# class_ab.net
KiCad netlist of a schematic drawn in Altium Designer
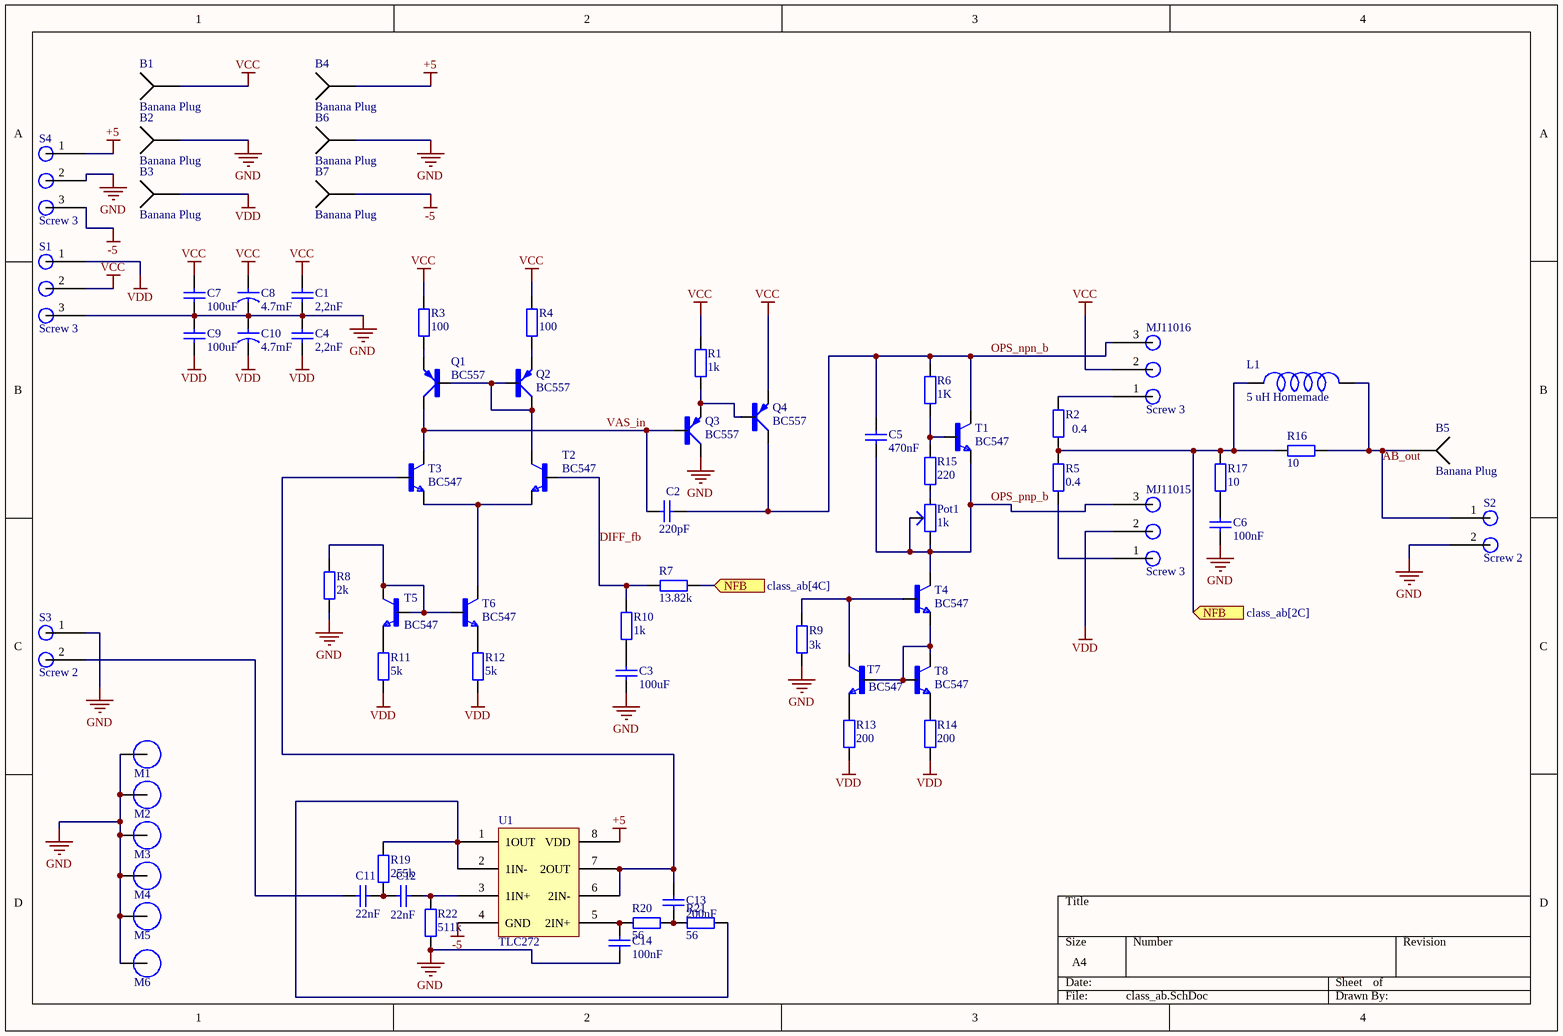
[diagram p0: class_ab.SchDoc]

(export (version "E")
  (design (tool "Eeschema 10.0.6"))
  (components
    (comp (ref "B1")
      (value "Banana Plug")
      (footprint "Banana Plug On top")
      (libsource (lib "AAURacing") (part "Banana Plug"))
    )
    (comp (ref "B2")
      (value "Banana Plug")
      (footprint "Banana Plug On top")
      (libsource (lib "AAURacing") (part "Banana Plug"))
    )
    (comp (ref "B3")
      (value "Banana Plug")
      (footprint "Banana Plug On top")
      (libsource (lib "AAURacing") (part "Banana Plug"))
    )
    (comp (ref "B4")
      (value "Banana Plug")
      (footprint "Banana Plug On top")
      (libsource (lib "AAURacing") (part "Banana Plug"))
    )
    (comp (ref "B5")
      (value "Banana Plug")
      (footprint "Banana Plug On top")
      (libsource (lib "AAURacing") (part "Banana Plug"))
    )
    (comp (ref "B6")
      (value "Banana Plug")
      (footprint "Banana Plug On top")
      (libsource (lib "AAURacing") (part "Banana Plug"))
    )
    (comp (ref "B7")
      (value "Banana Plug")
      (footprint "Banana Plug On top")
      (libsource (lib "AAURacing") (part "Banana Plug"))
    )
    (comp (ref "C1")
      (value "Cap")
      (footprint "Cap-1")
      (fields (field (name "CAPACITY") "2,2nF"))
      (libsource (lib "AAURacing") (part "Capacitor 1 space"))
    )
    (comp (ref "C2")
      (value "Cap")
      (footprint "Cap-0")
      (fields (field (name "CAPACITY") "220pF"))
      (libsource (lib "AAURacing") (part "Capacitor 0 space"))
    )
    (comp (ref "C3")
      (value "Cap")
      (footprint "Cap Ø8")
      (fields (field (name "CAPACITY") "100uF"))
      (libsource (lib "AAURacing") (part "Capacitor unpolarized"))
    )
    (comp (ref "C4")
      (value "Cap")
      (footprint "Cap-1")
      (fields (field (name "CAPACITY") "2,2nF"))
      (libsource (lib "AAURacing") (part "Capacitor 1 space"))
    )
    (comp (ref "C5")
      (value "Cap")
      (footprint "Cap-1")
      (fields (field (name "CAPACITY") "470nF"))
      (libsource (lib "AAURacing") (part "Capacitor 1 space"))
    )
    (comp (ref "C6")
      (value "Cap")
      (footprint "Cap-1")
      (fields (field (name "CAPACITY") "100nF"))
      (libsource (lib "AAURacing") (part "Capacitor 1 space"))
    )
    (comp (ref "C7")
      (value "Cap")
      (footprint "Cap Ø8")
      (fields (field (name "CAPACITY") "100uF"))
      (libsource (lib "AAURacing") (part "Capacitor unpolarized"))
    )
    (comp (ref "C8")
      (value "Cap")
      (footprint "Cap Lyt Ø18")
      (fields (field (name "CAPACITY") "4.7mF"))
      (libsource (lib "AAURacing") (part "Capacitor electrolytic"))
    )
    (comp (ref "C9")
      (value "Cap")
      (footprint "Cap Ø8")
      (fields (field (name "CAPACITY") "100uF"))
      (libsource (lib "AAURacing") (part "Capacitor unpolarized"))
    )
    (comp (ref "C10")
      (value "Cap")
      (footprint "Cap Lyt Ø18")
      (fields (field (name "CAPACITY") "4.7mF"))
      (libsource (lib "AAURacing") (part "Capacitor electrolytic"))
    )
    (comp (ref "C11")
      (value "Cap")
      (footprint "Cap-1")
      (fields (field (name "CAPACITY") "22nF"))
      (libsource (lib "AAURacing") (part "Capacitor 1 space"))
    )
    (comp (ref "C12")
      (value "Cap")
      (footprint "Cap-1")
      (fields (field (name "CAPACITY") "22nF"))
      (libsource (lib "AAURacing") (part "Capacitor 1 space"))
    )
    (comp (ref "C13")
      (value "Cap")
      (footprint "Cap-1")
      (fields (field (name "CAPACITY") "200nF"))
      (libsource (lib "AAURacing") (part "Capacitor 1 space"))
    )
    (comp (ref "C14")
      (value "Cap")
      (footprint "Cap-1")
      (fields (field (name "CAPACITY") "100nF"))
      (libsource (lib "AAURacing") (part "Capacitor 1 space"))
    )
    (comp (ref "L1")
      (value "5 uH Homemade")
      (footprint "homecooked inductor")
      (libsource (lib "esd410") (part "homemade inductor"))
    )
    (comp (ref "M1")
      (value "Screw Hole")
      (footprint "M3 Hole")
      (libsource (lib "AAURacing") (part "Screw Hole"))
    )
    (comp (ref "M2")
      (value "Screw Hole")
      (footprint "M3 Hole")
      (libsource (lib "AAURacing") (part "Screw Hole"))
    )
    (comp (ref "M3")
      (value "Screw Hole")
      (footprint "M3 Hole")
      (libsource (lib "AAURacing") (part "Screw Hole"))
    )
    (comp (ref "M4")
      (value "Screw Hole")
      (footprint "M3 Hole")
      (libsource (lib "AAURacing") (part "Screw Hole"))
    )
    (comp (ref "M5")
      (value "Screw Hole")
      (footprint "M3 Hole")
      (libsource (lib "AAURacing") (part "Screw Hole"))
    )
    (comp (ref "M6")
      (value "Screw Hole")
      (footprint "M3 Hole")
      (libsource (lib "AAURacing") (part "Screw Hole"))
    )
    (comp (ref "MJ11015")
      (value "Screw 3")
      (footprint "Screw-3")
      (libsource (lib "AAURacing") (part "Screw 3"))
    )
    (comp (ref "MJ11016")
      (value "Screw 3")
      (footprint "Screw-3")
      (libsource (lib "AAURacing") (part "Screw 3"))
    )
    (comp (ref "Pot1")
      (value "Pot Trim")
      (footprint "Pot trim slim high")
      (description "Potentiometer")
      (fields (field (name "RESISTANCE") "1k"))
      (libsource (lib "AAURacing") (part "Pot Trim"))
    )
    (comp (ref "Q1")
      (value "BC557")
      (footprint "SOT54A")
      (description "Bipolar (BJT) Transistor PNP 45 V 100 mA 320MHz 625 mW Through Hole TO-92 (TO-226)")
      (fields (field (name "MF") "ON"))
      (libsource (lib "BC557") (part "BC557"))
    )
    (comp (ref "Q2")
      (value "BC557")
      (footprint "SOT54A")
      (description "Bipolar (BJT) Transistor PNP 45 V 100 mA 320MHz 625 mW Through Hole TO-92 (TO-226)")
      (fields (field (name "MF") "ON"))
      (libsource (lib "") (part "BC557_1"))
    )
    (comp (ref "Q3")
      (value "BC557")
      (footprint "SOT54A")
      (description "Bipolar (BJT) Transistor PNP 45 V 100 mA 320MHz 625 mW Through Hole TO-92 (TO-226)")
      (fields (field (name "MF") "ON"))
      (libsource (lib "") (part "BC557_1"))
    )
    (comp (ref "Q4")
      (value "BC557")
      (footprint "SOT54A")
      (description "Bipolar (BJT) Transistor PNP 45 V 100 mA 320MHz 625 mW Through Hole TO-92 (TO-226)")
      (fields (field (name "MF") "ON"))
      (libsource (lib "") (part "BC557_1"))
    )
    (comp (ref "R1")
      (value "Resistor")
      (footprint "RES THT 9mm")
      (fields (field (name "OHM") "1k"))
      (libsource (lib "AAURacing") (part "Resistor"))
    )
    (comp (ref "R2")
      (value "Resistor")
      (footprint "RES THT 30mm")
      (fields (field (name "OHM") "0.4"))
      (libsource (lib "AAURacing") (part "Resistor"))
    )
    (comp (ref "R3")
      (value "Resistor")
      (footprint "RES THT 9mm")
      (fields (field (name "OHM") "100"))
      (libsource (lib "AAURacing") (part "Resistor"))
    )
    (comp (ref "R4")
      (value "Resistor")
      (footprint "RES THT 9mm")
      (fields (field (name "OHM") "100"))
      (libsource (lib "AAURacing") (part "Resistor"))
    )
    (comp (ref "R5")
      (value "Resistor")
      (footprint "RES THT 30mm")
      (fields (field (name "OHM") "0.4"))
      (libsource (lib "AAURacing") (part "Resistor"))
    )
    (comp (ref "R6")
      (value "Resistor")
      (footprint "RES THT 9mm")
      (fields (field (name "OHM") "1K"))
      (libsource (lib "AAURacing") (part "Resistor"))
    )
    (comp (ref "R7")
      (value "Resistor")
      (footprint "RES THT 9mm")
      (fields (field (name "OHM") "13.82k"))
      (libsource (lib "AAURacing") (part "Resistor"))
    )
    (comp (ref "R8")
      (value "Resistor")
      (footprint "RES THT 9mm")
      (fields (field (name "OHM") "2k"))
      (libsource (lib "AAURacing") (part "Resistor"))
    )
    (comp (ref "R9")
      (value "Resistor")
      (footprint "RES THT 9mm")
      (fields (field (name "OHM") "3k"))
      (libsource (lib "AAURacing") (part "Resistor"))
    )
    (comp (ref "R10")
      (value "Resistor")
      (footprint "RES THT 9mm")
      (fields (field (name "OHM") "1k"))
      (libsource (lib "AAURacing") (part "Resistor"))
    )
    (comp (ref "R11")
      (value "Resistor")
      (footprint "RES THT 9mm")
      (fields (field (name "OHM") "5k"))
      (libsource (lib "AAURacing") (part "Resistor"))
    )
    (comp (ref "R12")
      (value "Resistor")
      (footprint "RES THT 9mm")
      (fields (field (name "OHM") "5k"))
      (libsource (lib "AAURacing") (part "Resistor"))
    )
    (comp (ref "R13")
      (value "Resistor")
      (footprint "RES THT 9mm")
      (fields (field (name "OHM") "200"))
      (libsource (lib "AAURacing") (part "Resistor"))
    )
    (comp (ref "R14")
      (value "Resistor")
      (footprint "RES THT 9mm")
      (fields (field (name "OHM") "200"))
      (libsource (lib "AAURacing") (part "Resistor"))
    )
    (comp (ref "R15")
      (value "Resistor")
      (footprint "RES THT 9mm")
      (fields (field (name "OHM") "220"))
      (libsource (lib "AAURacing") (part "Resistor"))
    )
    (comp (ref "R16")
      (value "Resistor")
      (footprint "RES THT 9mm")
      (fields (field (name "OHM") "10"))
      (libsource (lib "AAURacing") (part "Resistor"))
    )
    (comp (ref "R17")
      (value "Resistor")
      (footprint "Power RES 5 watt")
      (fields (field (name "OHM") "10"))
      (libsource (lib "AAURacing") (part "Resistor"))
    )
    (comp (ref "R19")
      (value "Resistor")
      (footprint "RES THT 9mm")
      (fields (field (name "OHM") "255k"))
      (libsource (lib "AAURacing") (part "Resistor"))
    )
    (comp (ref "R20")
      (value "Resistor")
      (footprint "RES THT 9mm")
      (fields (field (name "OHM") "56"))
      (libsource (lib "AAURacing") (part "Resistor"))
    )
    (comp (ref "R21")
      (value "Resistor")
      (footprint "RES THT 9mm")
      (fields (field (name "OHM") "56"))
      (libsource (lib "AAURacing") (part "Resistor"))
    )
    (comp (ref "R22")
      (value "Resistor")
      (footprint "RES THT 9mm")
      (fields (field (name "OHM") "511k"))
      (libsource (lib "AAURacing") (part "Resistor"))
    )
    (comp (ref "S1") (value "Screw 3") (footprint "Screw-3") (libsource (lib "AAURacing") (part "Screw 3")))
    (comp (ref "S2") (value "Screw 2") (footprint "Screw-2") (libsource (lib "AAURacing") (part "Screw 2")))
    (comp (ref "S3") (value "Screw 2") (footprint "Screw-2") (libsource (lib "AAURacing") (part "Screw 2")))
    (comp (ref "S4") (value "Screw 3") (footprint "Screw-3") (libsource (lib "AAURacing") (part "Screw 3")))
    (comp (ref "T1")
      (value "BC547")
      (footprint "TO92")
      (description "Trans GP BJT NPN 45V 0.1A 500mW 3-Pin TO-92 T/R")
      (fields (field (name "MF") "ON Semiconductor"))
      (libsource (lib "") (part "BC547_1"))
    )
    (comp (ref "T2")
      (value "BC547")
      (footprint "TO92")
      (description "Trans GP BJT NPN 45V 0.1A 500mW 3-Pin TO-92 T/R")
      (fields (field (name "MF") "ON Semiconductor"))
      (libsource (lib "BC547") (part "BC547"))
    )
    (comp (ref "T3")
      (value "BC547")
      (footprint "TO92")
      (description "Trans GP BJT NPN 45V 0.1A 500mW 3-Pin TO-92 T/R")
      (fields (field (name "MF") "ON Semiconductor"))
      (libsource (lib "") (part "BC547_1"))
    )
    (comp (ref "T4")
      (value "BC547")
      (footprint "TO92")
      (description "Trans GP BJT NPN 45V 0.1A 500mW 3-Pin TO-92 T/R")
      (fields (field (name "MF") "ON Semiconductor"))
      (libsource (lib "") (part "BC547_1"))
    )
    (comp (ref "T5")
      (value "BC547")
      (footprint "TO92")
      (description "Trans GP BJT NPN 45V 0.1A 500mW 3-Pin TO-92 T/R")
      (fields (field (name "MF") "ON Semiconductor"))
      (libsource (lib "BC547") (part "BC547"))
    )
    (comp (ref "T6")
      (value "BC547")
      (footprint "TO92")
      (description "Trans GP BJT NPN 45V 0.1A 500mW 3-Pin TO-92 T/R")
      (fields (field (name "MF") "ON Semiconductor"))
      (libsource (lib "") (part "BC547_1"))
    )
    (comp (ref "T7")
      (value "BC547")
      (footprint "TO92")
      (description "Trans GP BJT NPN 45V 0.1A 500mW 3-Pin TO-92 T/R")
      (fields (field (name "MF") "ON Semiconductor"))
      (libsource (lib "BC547") (part "BC547"))
    )
    (comp (ref "T8")
      (value "BC547")
      (footprint "TO92")
      (description "Trans GP BJT NPN 45V 0.1A 500mW 3-Pin TO-92 T/R")
      (fields (field (name "MF") "ON Semiconductor"))
      (libsource (lib "") (part "BC547_1"))
    )
    (comp (ref "U1")
      (value "TLC272")
      (footprint "DIP-8")
      (description "PRECISION DUAL OPERATIONAL AMPLIFIER")
      (libsource (lib "AAURacing") (part "TLC272"))
    )
  )
  (nets
    (net (code "1") (name "+5") (class "Default")
      (node (ref "B4") (pin "1") (pinfunction "1_1") (pintype "passive"))
      (node (ref "S4") (pin "1") (pinfunction "1_1") (pintype "passive"))
      (node (ref "U1") (pin "8") (pinfunction "VDD_8") (pintype "passive"))
    )
    (net (code "2") (name "-5") (class "Default")
      (node (ref "B7") (pin "1") (pinfunction "1_1") (pintype "passive"))
      (node (ref "S4") (pin "3") (pinfunction "3_3") (pintype "passive"))
      (node (ref "U1") (pin "4") (pinfunction "GND_4") (pintype "passive"))
    )
    (net (code "3") (name "/AB_out") (class "Default")
      (node (ref "B5") (pin "1") (pinfunction "1_1") (pintype "passive"))
      (node (ref "L1") (pin "2") (pintype "passive"))
      (node (ref "R16") (pin "1") (pinfunction "1_1") (pintype "passive"))
      (node (ref "S2") (pin "1") (pinfunction "1_1") (pintype "passive"))
    )
    (net (code "4") (name "/DIFF_fb") (class "Default")
      (node (ref "R10") (pin "1") (pinfunction "1_1") (pintype "passive"))
      (node (ref "R7") (pin "2") (pinfunction "2_2") (pintype "passive"))
      (node (ref "T2") (pin "2") (pinfunction "B_2") (pintype "passive"))
    )
    (net (code "5") (name "/NFB") (class "Default")
      (node (ref "L1") (pin "1") (pintype "passive"))
      (node (ref "R16") (pin "2") (pinfunction "2_2") (pintype "passive"))
      (node (ref "R17") (pin "2") (pinfunction "2_2") (pintype "passive"))
      (node (ref "R2") (pin "1") (pinfunction "1_1") (pintype "passive"))
      (node (ref "R5") (pin "2") (pinfunction "2_2") (pintype "passive"))
      (node (ref "R7") (pin "1") (pinfunction "1_1") (pintype "passive"))
    )
    (net (code "6") (name "/OPS_npn_b") (class "Default")
      (node (ref "C2") (pin "2") (pinfunction "g_2") (pintype "passive"))
      (node (ref "C5") (pin "2") (pinfunction "g_2") (pintype "passive"))
      (node (ref "MJ11016") (pin "3") (pinfunction "3_3") (pintype "passive"))
      (node (ref "Q4") (pin "C") (pinfunction "C_C") (pintype "passive"))
      (node (ref "R6") (pin "2") (pinfunction "2_2") (pintype "passive"))
      (node (ref "T1") (pin "1") (pinfunction "C_1") (pintype "passive"))
    )
    (net (code "7") (name "/OPS_pnp_b") (class "Default")
      (node (ref "C5") (pin "1") (pinfunction "1_1") (pintype "passive"))
      (node (ref "MJ11015") (pin "3") (pinfunction "3_3") (pintype "passive"))
      (node (ref "Pot1") (pin "2") (pinfunction "2_2") (pintype "passive"))
      (node (ref "Pot1") (pin "3") (pinfunction "3_3") (pintype "passive"))
      (node (ref "T1") (pin "3") (pinfunction "E_3") (pintype "passive"))
      (node (ref "T4") (pin "1") (pinfunction "C_1") (pintype "passive"))
    )
    (net (code "8") (name "/VAS_in") (class "Default")
      (node (ref "C2") (pin "1") (pinfunction "1_1") (pintype "passive"))
      (node (ref "Q1") (pin "C") (pinfunction "C_C") (pintype "passive"))
      (node (ref "Q3") (pin "B") (pinfunction "B_B") (pintype "passive"))
      (node (ref "T3") (pin "1") (pinfunction "C_1") (pintype "passive"))
    )
    (net (code "9") (name "GND") (class "Default")
      (node (ref "B2") (pin "1") (pinfunction "1_1") (pintype "passive"))
      (node (ref "B6") (pin "1") (pinfunction "1_1") (pintype "passive"))
      (node (ref "C1") (pin "1") (pinfunction "1_1") (pintype "passive"))
      (node (ref "C10") (pin "1") (pinfunction "1_1") (pintype "passive"))
      (node (ref "C14") (pin "2") (pinfunction "g_2") (pintype "passive"))
      (node (ref "C3") (pin "1") (pinfunction "1_1") (pintype "passive"))
      (node (ref "C4") (pin "2") (pinfunction "g_2") (pintype "passive"))
      (node (ref "C6") (pin "1") (pinfunction "1_1") (pintype "passive"))
      (node (ref "C7") (pin "1") (pinfunction "1_1") (pintype "passive"))
      (node (ref "C8") (pin "2") (pinfunction "g_2") (pintype "passive"))
      (node (ref "C9") (pin "2") (pinfunction "g_2") (pintype "passive"))
      (node (ref "M1") (pin "1") (pinfunction "1_1") (pintype "passive"))
      (node (ref "M2") (pin "1") (pinfunction "1_1") (pintype "passive"))
      (node (ref "M3") (pin "1") (pinfunction "1_1") (pintype "passive"))
      (node (ref "M4") (pin "1") (pinfunction "1_1") (pintype "passive"))
      (node (ref "M5") (pin "1") (pinfunction "1_1") (pintype "passive"))
      (node (ref "M6") (pin "1") (pinfunction "1_1") (pintype "passive"))
      (node (ref "Q3") (pin "C") (pinfunction "C_C") (pintype "passive"))
      (node (ref "R22") (pin "1") (pinfunction "1_1") (pintype "passive"))
      (node (ref "R8") (pin "1") (pinfunction "1_1") (pintype "passive"))
      (node (ref "R9") (pin "1") (pinfunction "1_1") (pintype "passive"))
      (node (ref "S1") (pin "3") (pinfunction "3_3") (pintype "passive"))
      (node (ref "S2") (pin "2") (pinfunction "2_2") (pintype "passive"))
      (node (ref "S3") (pin "1") (pinfunction "1_1") (pintype "passive"))
      (node (ref "S4") (pin "2") (pinfunction "2_2") (pintype "passive"))
    )
    (net (code "10") (name "Net-(C3-g)") (class "Default")
      (node (ref "C3") (pin "2") (pinfunction "g_2") (pintype "passive"))
      (node (ref "R10") (pin "2") (pinfunction "2_2") (pintype "passive"))
    )
    (net (code "11") (name "Net-(C6-g)") (class "Default")
      (node (ref "C6") (pin "2") (pinfunction "g_2") (pintype "passive"))
      (node (ref "R17") (pin "1") (pinfunction "1_1") (pintype "passive"))
    )
    (net (code "12") (name "Net-(C11-g)") (class "Default")
      (node (ref "C11") (pin "2") (pinfunction "g_2") (pintype "passive"))
      (node (ref "S3") (pin "2") (pinfunction "2_2") (pintype "passive"))
    )
    (net (code "13") (name "Net-(C12-g)") (class "Default")
      (node (ref "C11") (pin "1") (pinfunction "1_1") (pintype "passive"))
      (node (ref "C12") (pin "2") (pinfunction "g_2") (pintype "passive"))
      (node (ref "R19") (pin "1") (pinfunction "1_1") (pintype "passive"))
    )
    (net (code "14") (name "Net-(C13-g)") (class "Default")
      (node (ref "C13") (pin "2") (pinfunction "g_2") (pintype "passive"))
      (node (ref "R20") (pin "1") (pinfunction "1_1") (pintype "passive"))
      (node (ref "R21") (pin "2") (pinfunction "2_2") (pintype "passive"))
    )
    (net (code "15") (name "Net-(MJ11015-Pad1)") (class "Default")
      (node (ref "MJ11015") (pin "1") (pinfunction "1_1") (pintype "passive"))
      (node (ref "R5") (pin "1") (pinfunction "1_1") (pintype "passive"))
    )
    (net (code "16") (name "Net-(MJ11016-Pad1)") (class "Default")
      (node (ref "MJ11016") (pin "1") (pinfunction "1_1") (pintype "passive"))
      (node (ref "R2") (pin "2") (pinfunction "2_2") (pintype "passive"))
    )
    (net (code "17") (name "Net-(Pot1-Pad1)") (class "Default")
      (node (ref "Pot1") (pin "1") (pinfunction "1_1") (pintype "passive"))
      (node (ref "R15") (pin "1") (pinfunction "1_1") (pintype "passive"))
    )
    (net (code "18") (name "Net-(Q1-PadE)") (class "Default")
      (node (ref "Q1") (pin "E") (pinfunction "E_E") (pintype "passive"))
      (node (ref "R3") (pin "1") (pinfunction "1_1") (pintype "passive"))
    )
    (net (code "19") (name "Net-(Q2-PadE)") (class "Default")
      (node (ref "Q2") (pin "E") (pinfunction "E_E") (pintype "passive"))
      (node (ref "R4") (pin "1") (pinfunction "1_1") (pintype "passive"))
    )
    (net (code "20") (name "Net-(Q3-PadE)") (class "Default")
      (node (ref "Q3") (pin "E") (pinfunction "E_E") (pintype "passive"))
      (node (ref "Q4") (pin "B") (pinfunction "B_B") (pintype "passive"))
      (node (ref "R1") (pin "1") (pinfunction "1_1") (pintype "passive"))
    )
    (net (code "21") (name "Net-(T1-B)") (class "Default")
      (node (ref "R15") (pin "2") (pinfunction "2_2") (pintype "passive"))
      (node (ref "R6") (pin "1") (pinfunction "1_1") (pintype "passive"))
      (node (ref "T1") (pin "2") (pinfunction "B_2") (pintype "passive"))
    )
    (net (code "22") (name "Net-(T2-C)") (class "Default")
      (node (ref "Q1") (pin "B") (pinfunction "B_B") (pintype "passive"))
      (node (ref "Q2") (pin "B") (pinfunction "B_B") (pintype "passive"))
      (node (ref "Q2") (pin "C") (pinfunction "C_C") (pintype "passive"))
      (node (ref "T2") (pin "1") (pinfunction "C_1") (pintype "passive"))
    )
    (net (code "23") (name "Net-(T2-E)") (class "Default")
      (node (ref "T2") (pin "3") (pinfunction "E_3") (pintype "passive"))
      (node (ref "T3") (pin "3") (pinfunction "E_3") (pintype "passive"))
      (node (ref "T6") (pin "1") (pinfunction "C_1") (pintype "passive"))
    )
    (net (code "24") (name "Net-(T3-B)") (class "Default")
      (node (ref "C13") (pin "1") (pinfunction "1_1") (pintype "passive"))
      (node (ref "T3") (pin "2") (pinfunction "B_2") (pintype "passive"))
      (node (ref "U1") (pin "6") (pinfunction "2IN-_6") (pintype "passive"))
      (node (ref "U1") (pin "7") (pinfunction "2OUT_7") (pintype "passive"))
    )
    (net (code "25") (name "Net-(T4-B)") (class "Default")
      (node (ref "R9") (pin "2") (pinfunction "2_2") (pintype "passive"))
      (node (ref "T4") (pin "2") (pinfunction "B_2") (pintype "passive"))
      (node (ref "T7") (pin "1") (pinfunction "C_1") (pintype "passive"))
    )
    (net (code "26") (name "Net-(T4-E)") (class "Default")
      (node (ref "T4") (pin "3") (pinfunction "E_3") (pintype "passive"))
      (node (ref "T7") (pin "2") (pinfunction "B_2") (pintype "passive"))
      (node (ref "T8") (pin "1") (pinfunction "C_1") (pintype "passive"))
      (node (ref "T8") (pin "2") (pinfunction "B_2") (pintype "passive"))
    )
    (net (code "27") (name "Net-(T5-B)") (class "Default")
      (node (ref "R8") (pin "2") (pinfunction "2_2") (pintype "passive"))
      (node (ref "T5") (pin "1") (pinfunction "C_1") (pintype "passive"))
      (node (ref "T5") (pin "2") (pinfunction "B_2") (pintype "passive"))
      (node (ref "T6") (pin "2") (pinfunction "B_2") (pintype "passive"))
    )
    (net (code "28") (name "Net-(T5-E)") (class "Default")
      (node (ref "R11") (pin "2") (pinfunction "2_2") (pintype "passive"))
      (node (ref "T5") (pin "3") (pinfunction "E_3") (pintype "passive"))
    )
    (net (code "29") (name "Net-(T6-E)") (class "Default")
      (node (ref "R12") (pin "2") (pinfunction "2_2") (pintype "passive"))
      (node (ref "T6") (pin "3") (pinfunction "E_3") (pintype "passive"))
    )
    (net (code "30") (name "Net-(T7-E)") (class "Default")
      (node (ref "R13") (pin "2") (pinfunction "2_2") (pintype "passive"))
      (node (ref "T7") (pin "3") (pinfunction "E_3") (pintype "passive"))
    )
    (net (code "31") (name "Net-(T8-E)") (class "Default")
      (node (ref "R14") (pin "2") (pinfunction "2_2") (pintype "passive"))
      (node (ref "T8") (pin "3") (pinfunction "E_3") (pintype "passive"))
    )
    (net (code "32") (name "Net-(U1-1IN+)") (class "Default")
      (node (ref "C12") (pin "1") (pinfunction "1_1") (pintype "passive"))
      (node (ref "R22") (pin "2") (pinfunction "2_2") (pintype "passive"))
      (node (ref "U1") (pin "3") (pinfunction "1IN+_3") (pintype "passive"))
    )
    (net (code "33") (name "Net-(U1-1IN-)") (class "Default")
      (node (ref "R19") (pin "2") (pinfunction "2_2") (pintype "passive"))
      (node (ref "R21") (pin "1") (pinfunction "1_1") (pintype "passive"))
      (node (ref "U1") (pin "1") (pinfunction "1OUT_1") (pintype "passive"))
      (node (ref "U1") (pin "2") (pinfunction "1IN-_2") (pintype "passive"))
    )
    (net (code "34") (name "Net-(U1-2IN+)") (class "Default")
      (node (ref "C14") (pin "1") (pinfunction "1_1") (pintype "passive"))
      (node (ref "R20") (pin "2") (pinfunction "2_2") (pintype "passive"))
      (node (ref "U1") (pin "5") (pinfunction "2IN+_5") (pintype "passive"))
    )
    (net (code "35") (name "VCC") (class "Default")
      (node (ref "B1") (pin "1") (pinfunction "1_1") (pintype "passive"))
      (node (ref "C1") (pin "2") (pinfunction "g_2") (pintype "passive"))
      (node (ref "C7") (pin "2") (pinfunction "g_2") (pintype "passive"))
      (node (ref "C8") (pin "1") (pinfunction "1_1") (pintype "passive"))
      (node (ref "MJ11016") (pin "2") (pinfunction "2_2") (pintype "passive"))
      (node (ref "Q4") (pin "E") (pinfunction "E_E") (pintype "passive"))
      (node (ref "R1") (pin "2") (pinfunction "2_2") (pintype "passive"))
      (node (ref "R3") (pin "2") (pinfunction "2_2") (pintype "passive"))
      (node (ref "R4") (pin "2") (pinfunction "2_2") (pintype "passive"))
      (node (ref "S1") (pin "2") (pinfunction "2_2") (pintype "passive"))
    )
    (net (code "36") (name "VDD") (class "Default")
      (node (ref "B3") (pin "1") (pinfunction "1_1") (pintype "passive"))
      (node (ref "C10") (pin "2") (pinfunction "g_2") (pintype "passive"))
      (node (ref "C4") (pin "1") (pinfunction "1_1") (pintype "passive"))
      (node (ref "C9") (pin "1") (pinfunction "1_1") (pintype "passive"))
      (node (ref "MJ11015") (pin "2") (pinfunction "2_2") (pintype "passive"))
      (node (ref "R11") (pin "1") (pinfunction "1_1") (pintype "passive"))
      (node (ref "R12") (pin "1") (pinfunction "1_1") (pintype "passive"))
      (node (ref "R13") (pin "1") (pinfunction "1_1") (pintype "passive"))
      (node (ref "R14") (pin "1") (pinfunction "1_1") (pintype "passive"))
      (node (ref "S1") (pin "1") (pinfunction "1_1") (pintype "passive"))
    )
  )
)
